# conectores.net
KiCad netlist of a schematic drawn in EAGLE
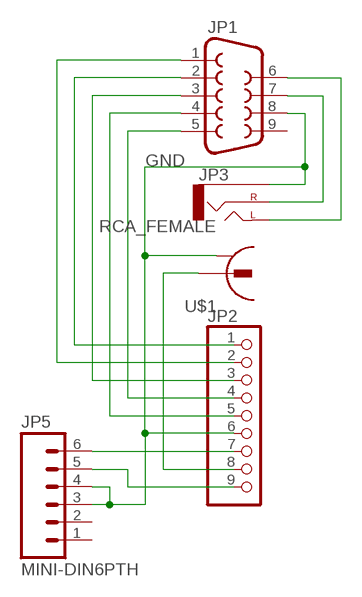
[diagram p0: schematic, sheet 1]

(export (version "E")
  (design (tool "Eeschema 10.0.6"))
  (components
    (comp (ref "JP1")
      (value "DB9MALE")
      (footprint "eagle-import:DB9_MALE")
      (libsource (lib "eagle-import") (part "DB9MALE"))
    )
    (comp (ref "JP2")
      (value "PINHD-1X9")
      (footprint "eagle-import:1X09")
      (libsource (lib "eagle-import") (part "PINHD-1X9"))
    )
    (comp (ref "JP3")
      (value "AUDIO-JACKPTH")
      (footprint "eagle-import:AUDIO-JACK")
      (libsource (lib "eagle-import") (part "AUDIO-JACKPTH"))
    )
    (comp (ref "JP5")
      (value "MINI-DIN6PTH")
      (footprint "eagle-import:MINI-DIN6")
      (libsource (lib "eagle-import") (part "MINI-DIN6PTH"))
    )
    (comp (ref "U$1")
      (value "RCA_FEMALE")
      (footprint "eagle-import:RCA_EBAY")
      (libsource (lib "eagle-import") (part "RCA_FEMALE"))
    )
  )
  (nets
    (net (code "1") (name "/GND") (class "Default")
      (node (ref "JP1") (pin "8") (pinfunction "8_8") (pintype "passive"))
      (node (ref "JP2") (pin "6") (pinfunction "6_6") (pintype "passive"))
      (node (ref "JP3") (pin "SLEEVE") (pinfunction "SLEEVE_SLEEVE") (pintype "bidirectional"))
      (node (ref "JP5") (pin "3") (pinfunction "3_3") (pintype "passive"))
      (node (ref "JP5") (pin "4") (pinfunction "4_4") (pintype "passive"))
      (node (ref "U$1") (pin "1") (pinfunction "2_1") (pintype "passive"))
    )
    (net (code "2") (name "Net-(JP1-Pad1)") (class "Default")
      (node (ref "JP1") (pin "1") (pinfunction "1_1") (pintype "passive"))
      (node (ref "JP2") (pin "2") (pinfunction "2_2") (pintype "passive"))
    )
    (net (code "3") (name "Net-(JP1-Pad2)") (class "Default")
      (node (ref "JP1") (pin "2") (pinfunction "2_2") (pintype "passive"))
      (node (ref "JP2") (pin "1") (pinfunction "1_1") (pintype "passive"))
    )
    (net (code "4") (name "Net-(JP1-Pad3)") (class "Default")
      (node (ref "JP1") (pin "3") (pinfunction "3_3") (pintype "passive"))
      (node (ref "JP2") (pin "3") (pinfunction "3_3") (pintype "passive"))
    )
    (net (code "5") (name "Net-(JP1-Pad4)") (class "Default")
      (node (ref "JP1") (pin "4") (pinfunction "4_4") (pintype "passive"))
      (node (ref "JP2") (pin "5") (pinfunction "5_5") (pintype "passive"))
    )
    (net (code "6") (name "Net-(JP1-Pad5)") (class "Default")
      (node (ref "JP1") (pin "5") (pinfunction "5_5") (pintype "passive"))
      (node (ref "JP2") (pin "4") (pinfunction "4_4") (pintype "passive"))
    )
    (net (code "7") (name "Net-(JP2-Pad7)") (class "Default")
      (node (ref "JP2") (pin "7") (pinfunction "7_7") (pintype "passive"))
      (node (ref "JP5") (pin "6") (pinfunction "6_6") (pintype "passive"))
    )
    (net (code "8") (name "Net-(JP2-Pad9)") (class "Default")
      (node (ref "JP2") (pin "9") (pinfunction "9_9") (pintype "passive"))
      (node (ref "JP5") (pin "5") (pinfunction "5_5") (pintype "passive"))
    )
    (net (code "9") (name "Net-(JP3-LEFT)") (class "Default")
      (node (ref "JP1") (pin "6") (pinfunction "6_6") (pintype "passive"))
      (node (ref "JP3") (pin "TIP") (pinfunction "LEFT_TIP") (pintype "bidirectional"))
    )
    (net (code "10") (name "Net-(JP3-RIGHT)") (class "Default")
      (node (ref "JP1") (pin "7") (pinfunction "7_7") (pintype "passive"))
      (node (ref "JP3") (pin "RING") (pinfunction "RIGHT_RING") (pintype "bidirectional"))
    )
    (net (code "11") (name "Net-(U$1-1)") (class "Default")
      (node (ref "JP2") (pin "8") (pinfunction "8_8") (pintype "passive"))
      (node (ref "U$1") (pin "2") (pinfunction "1_2") (pintype "passive"))
    )
    (net (code "12") (name "unconnected-(JP1-Pad9)") (class "Default")
      (node (ref "JP1") (pin "9") (pinfunction "9_9") (pintype "passive"))
    )
    (net (code "13") (name "unconnected-(JP5-Pad1)") (class "Default")
      (node (ref "JP5") (pin "1") (pinfunction "1_1") (pintype "passive"))
    )
    (net (code "14") (name "unconnected-(JP5-Pad2)") (class "Default")
      (node (ref "JP5") (pin "2") (pinfunction "2_2") (pintype "passive"))
    )
  )
)
